# 4-20mA.net
KiCad netlist of a schematic drawn in Altium Designer
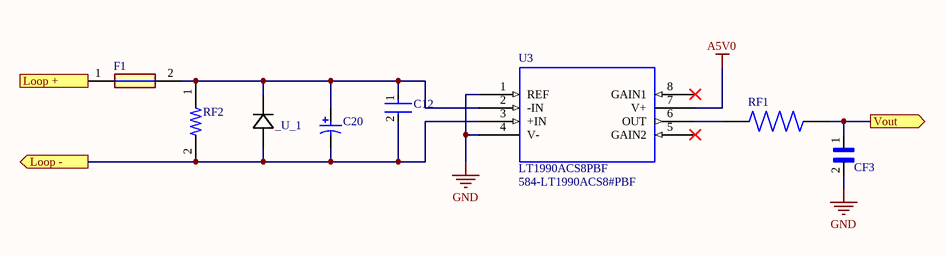
[diagram p0: 4-20mA.SchDoc]

(export (version "E")
  (design (tool "Eeschema 10.0.6"))
  (components
    (comp (ref "C12")
      (value "C0603C104K5RACTU")
      (footprint "FP-C0603C-CF-IPC_A")
      (description "Multilayer Ceramic Capacitors (MLCC) - SMD/SMT 50volts 0.1uF X7R 10%")
      (fields (field (name "MANUFACTURER") "KEMET") (field (name "TOLERANCE") "10%"))
      (libsource (lib "Replacements") (part "C0603C104K5RACTU"))
    )
    (comp (ref "C20")
      (value "UUD1V4R7MCL1GS")
      (footprint "NIC-CAPA2-4X5.8_V")
      (description "Cap Aluminum Lytic 4.7uF 35V 20% (4 X 5.8mm) SMD 80mA 2000h 105C Automotive T/R")
      (fields (field (name "MANUFACTURER") "Nichicon") (field (name "TOLERANCE") "20%"))
      (libsource (lib "Replacements") (part "UUD1V4R7MCL1GS"))
    )
    (comp (ref "CF3")
      (value "GCM188R71C105KA64J")
      (footprint "CAPC1608X90N")
      (description "0603 1 uF 16 V Â±10% Tolerance X7R Automotive Multilayer Ceramic Capacitor")
      (fields (field (name "MF") "Murata"))
      (libsource (lib "1uF_Cap_GCM188R71C105KA64J") (part "GCM188R71C105KA64J"))
    )
    (comp (ref "F1")
      (value "0ZCJ0005FF2E")
      (footprint "SamacSys:FUSC3216X85N")
      (description "Fuse")
      (libsource (lib "SamacSys") (part "0ZCJ0005FF2E"))
    )
    (comp (ref "RF1")
      (value "CRS2010AFX-1001ELF")
      (footprint "RESC5025X70N")
      (libsource (lib "1K_Res_CRS2010AFX-1001ELF") (part "CRS2010AFX-1001ELF"))
    )
    (comp (ref "RF2")
      (value "CRGS0805J100R")
      (footprint "RESC2012X65N")
      (description "100 Ohms Â±5% 0.5W, 1/2W Chip Resistor 0805 _2012 Metric_ Pulse Withstanding Thick Film")
      (fields (field (name "MF") "TE Connectivity"))
      (libsource (lib "100_Res_CRGS0805J100R") (part "CRGS0805J100R"))
    )
    (comp (ref "U3")
      (value "LT1990ACS8PBF")
      (footprint "SO-8_S")
      (description "SP Amp DIFF AMP Single R-R O/P ±18V/36V Automotive 8-Pin SOIC N Tube")
      (fields
        (field (name "MF") "Analog Devices")
        (field (name "MP") "LT1990ACS8#PBF")
        (field (name "SUPPLIER PART NUMBER 1") "584-LT1990ACS8#PBF")
      )
      (libsource (lib "Comparator_LT1990ACS8PBF") (part "LT1990ACS8PBF"))
    )
    (comp (ref "_U_1")
      (value "1KSMB39CA")
      (footprint "1KSMBSeries_LTF")
      (description "No Description Available")
      (fields (field (name "COPYRIGHT") "Copyright (C) 2021 Ultra Librarian. All rights reserved."))
      (libsource (lib "Diode_TVS_1KSMB39CA") (part "1KSMB39CA"))
    )
  )
  (nets
    (net (code "1") (name "/Loop +") (class "Default")
      (node (ref "F1") (pin "1") (pinfunction "1_1") (pintype "passive"))
    )
    (net (code "2") (name "/Loop -") (class "Default")
      (node (ref "C12") (pin "2") (pinfunction "2_2") (pintype "passive"))
      (node (ref "C20") (pin "2") (pinfunction "2_2") (pintype "passive"))
      (node (ref "RF2") (pin "2") (pinfunction "2_2") (pintype "passive"))
      (node (ref "U3") (pin "3") (pinfunction "+IN_3") (pintype "input"))
      (node (ref "_U_1") (pin "2") (pinfunction "12_2") (pintype "passive"))
    )
    (net (code "3") (name "/Vout") (class "Default")
      (node (ref "CF3") (pin "1") (pinfunction "1_1") (pintype "passive"))
      (node (ref "RF1") (pin "2") (pinfunction "2_2") (pintype "passive"))
    )
    (net (code "4") (name "A5V0") (class "Default")
      (node (ref "U3") (pin "7") (pinfunction "V+_7") (pintype "power_in"))
    )
    (net (code "5") (name "GND") (class "Default")
      (node (ref "CF3") (pin "2") (pinfunction "2_2") (pintype "passive"))
      (node (ref "U3") (pin "1") (pinfunction "REF_1") (pintype "input"))
      (node (ref "U3") (pin "4") (pinfunction "V-_4") (pintype "power_in"))
    )
    (net (code "6") (name "Net-(U3--IN)") (class "Default")
      (node (ref "C12") (pin "1") (pinfunction "1_1") (pintype "passive"))
      (node (ref "C20") (pin "1") (pinfunction "1_1") (pintype "passive"))
      (node (ref "F1") (pin "2") (pinfunction "2_2") (pintype "passive"))
      (node (ref "RF2") (pin "1") (pinfunction "1_1") (pintype "passive"))
      (node (ref "U3") (pin "2") (pinfunction "-IN_2") (pintype "input"))
      (node (ref "_U_1") (pin "1") (pinfunction "11_1") (pintype "passive"))
    )
    (net (code "7") (name "Net-(U3-OUT)") (class "Default")
      (node (ref "RF1") (pin "1") (pinfunction "1_1") (pintype "passive"))
      (node (ref "U3") (pin "6") (pinfunction "OUT_6") (pintype "output"))
    )
    (net (code "8") (name "unconnected-(U3-GAIN1-Pad8)") (class "Default")
      (node (ref "U3") (pin "8") (pinfunction "GAIN1_8") (pintype "input+no_connect"))
    )
    (net (code "9") (name "unconnected-(U3-GAIN2-Pad5)") (class "Default")
      (node (ref "U3") (pin "5") (pinfunction "GAIN2_5") (pintype "input+no_connect"))
    )
  )
)
